# LED_Array.net
KiCad netlist of a schematic drawn in Altium Designer
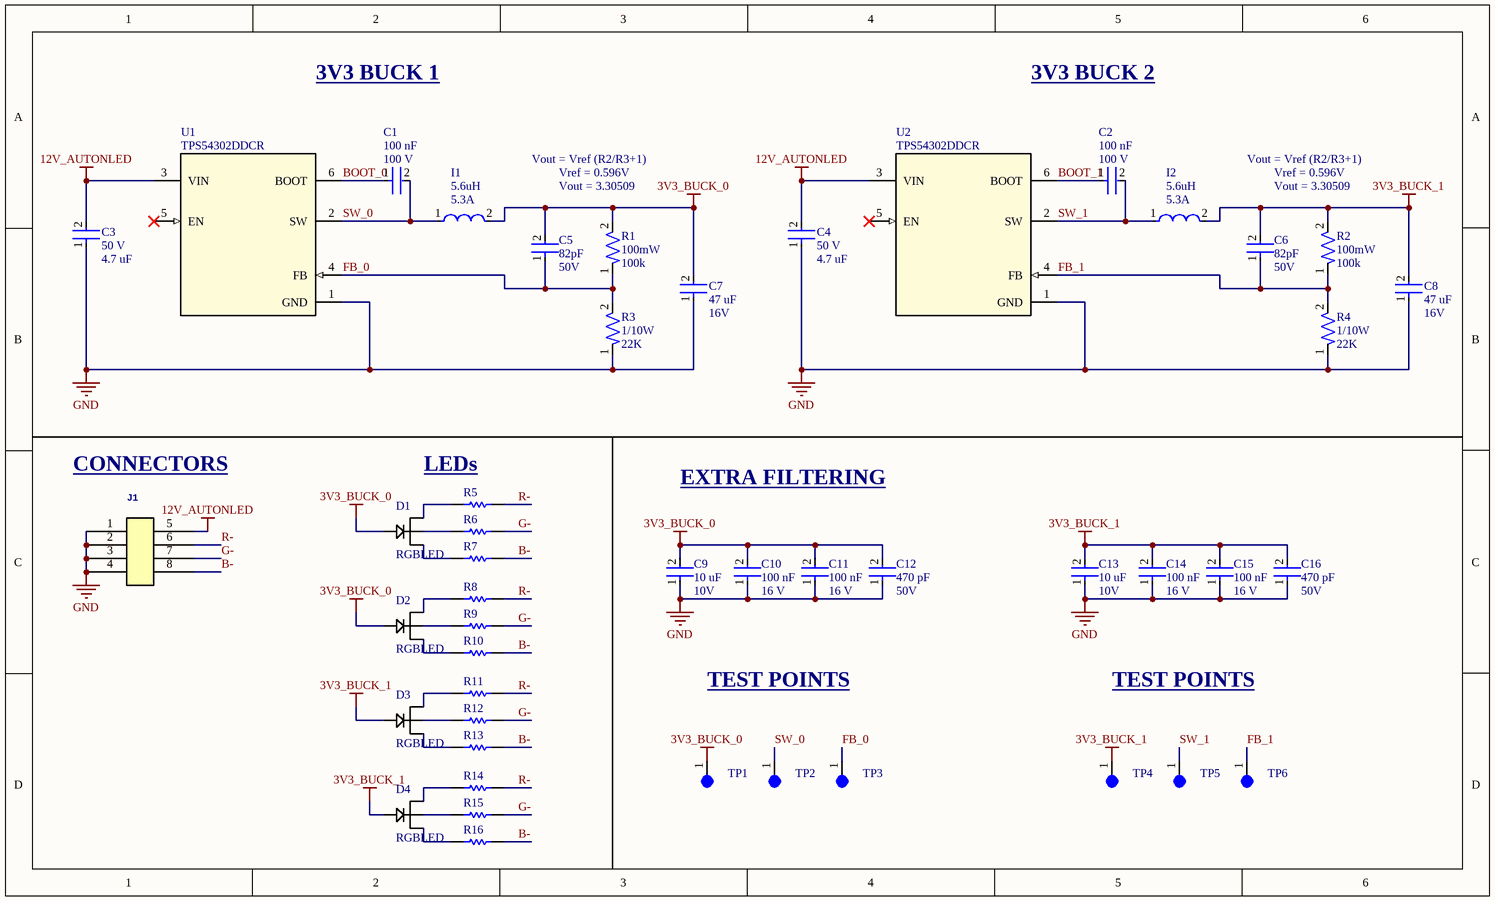
[diagram p0: LED_Array.SchDoc]

(export (version "E")
  (design (tool "Eeschema 10.0.6"))
  (components
    (comp (ref "C1")
      (value "CC0603KRX7R0BB104")
      (footprint "CAP-0603")
      (description "CAP CER 0.1UF 100V X7R 0603")
      (fields (field (name "CAPACITANCE") "100 nF") (field (name "VOLTAGE") "100 V"))
      (libsource (lib "JLC_25") (part "CAP-100N-0001"))
    )
    (comp (ref "C2")
      (value "CC0603KRX7R0BB104")
      (footprint "CAP-0603")
      (description "CAP CER 0.1UF 100V X7R 0603")
      (fields (field (name "CAPACITANCE") "100 nF") (field (name "VOLTAGE") "100 V"))
      (libsource (lib "JLC_25") (part "CAP-100N-0001"))
    )
    (comp (ref "C3")
      (value "CC0805KKX5R9BB475")
      (footprint "CAP-0805")
      (description "CAP CER 4.7UF 50V X5R 0805")
      (fields (field (name "VOLTAGE") "50 V") (field (name "CAPACITANCE") "4.7 uF"))
      (libsource (lib "JLC_25") (part "CAP-4.7U-0002"))
    )
    (comp (ref "C4")
      (value "CC0805KKX5R9BB475")
      (footprint "CAP-0805")
      (description "CAP CER 4.7UF 50V X5R 0805")
      (fields (field (name "VOLTAGE") "50 V") (field (name "CAPACITANCE") "4.7 uF"))
      (libsource (lib "JLC_25") (part "CAP-4.7U-0002"))
    )
    (comp (ref "C5")
      (value "CC0805JRNPO9BN820")
      (footprint "CAP-0805")
      (description "82 pF ±5% 50V Ceramic Capacitor C0G, NP0 0805 (2012 Metric)")
      (fields (field (name "VOLTAGE") "50V") (field (name "CAPACITANCE") "82pF"))
      (libsource (lib "JLC_25") (part "CAP-82P-0001"))
    )
    (comp (ref "C6")
      (value "CC0805JRNPO9BN820")
      (footprint "CAP-0805")
      (description "82 pF ±5% 50V Ceramic Capacitor C0G, NP0 0805 (2012 Metric)")
      (fields (field (name "VOLTAGE") "50V") (field (name "CAPACITANCE") "82pF"))
      (libsource (lib "JLC_25") (part "CAP-82P-0001"))
    )
    (comp (ref "C7")
      (value "GRM32ER61C476KE15L")
      (footprint "CAP-1210")
      (description "CAP CER 47UF 16V X5R 1210")
      (fields (field (name "CAPACITANCE") "47 uF") (field (name "VOLTAGE") "16V"))
      (libsource (lib "JLC_25") (part "CAP-47U-0002"))
    )
    (comp (ref "C8")
      (value "GRM32ER61C476KE15L")
      (footprint "CAP-1210")
      (description "CAP CER 47UF 16V X5R 1210")
      (fields (field (name "CAPACITANCE") "47 uF") (field (name "VOLTAGE") "16V"))
      (libsource (lib "JLC_25") (part "CAP-47U-0002"))
    )
    (comp (ref "C9")
      (value "CC0603KRX5R6BB106")
      (footprint "CAP-0603")
      (description "CAP CER 10UF 10V X5R 0603")
      (fields (field (name "VOLTAGE") "10V") (field (name "CAPACITANCE") "10 uF"))
      (libsource (lib "JLC_25") (part "CAP-10U-0001"))
    )
    (comp (ref "C10")
      (value "CC0402KRX7R7BB104")
      (footprint "CAP-0402")
      (description "CAP CER 0.1UF 16V X7R 0402")
      (fields (field (name "VOLTAGE RATING") "16 V") (field (name "CAPACITANCE") "100 nF"))
      (libsource (lib "JLC_25") (part "CAP-0.1U-0001"))
    )
    (comp (ref "C11")
      (value "CC0402KRX7R7BB104")
      (footprint "CAP-0402")
      (description "CAP CER 0.1UF 16V X7R 0402")
      (fields (field (name "VOLTAGE RATING") "16 V") (field (name "CAPACITANCE") "100 nF"))
      (libsource (lib "JLC_25") (part "CAP-0.1U-0001"))
    )
    (comp (ref "C12")
      (value "CC0805JRNPO9BN471")
      (footprint "CAP-0805")
      (description "CAP CER 470PF 50V C0G/NPO 0805")
      (fields (field (name "VOLTAGE") "50V") (field (name "CAPACITANCE") "470 pF"))
      (libsource (lib "JLC_25") (part "CAP-470P-0001"))
    )
    (comp (ref "C13")
      (value "CC0603KRX5R6BB106")
      (footprint "CAP-0603")
      (description "CAP CER 10UF 10V X5R 0603")
      (fields (field (name "VOLTAGE") "10V") (field (name "CAPACITANCE") "10 uF"))
      (libsource (lib "JLC_25") (part "CAP-10U-0001"))
    )
    (comp (ref "C14")
      (value "CC0402KRX7R7BB104")
      (footprint "CAP-0402")
      (description "CAP CER 0.1UF 16V X7R 0402")
      (fields (field (name "VOLTAGE RATING") "16 V") (field (name "CAPACITANCE") "100 nF"))
      (libsource (lib "JLC_25") (part "CAP-0.1U-0001"))
    )
    (comp (ref "C15")
      (value "CC0402KRX7R7BB104")
      (footprint "CAP-0402")
      (description "CAP CER 0.1UF 16V X7R 0402")
      (fields (field (name "VOLTAGE RATING") "16 V") (field (name "CAPACITANCE") "100 nF"))
      (libsource (lib "JLC_25") (part "CAP-0.1U-0001"))
    )
    (comp (ref "C16")
      (value "CC0805JRNPO9BN471")
      (footprint "CAP-0805")
      (description "CAP CER 470PF 50V C0G/NPO 0805")
      (fields (field (name "VOLTAGE") "50V") (field (name "CAPACITANCE") "470 pF"))
      (libsource (lib "JLC_25") (part "CAP-470P-0001"))
    )
    (comp (ref "D1")
      (value "RGBLED")
      (footprint "RGBLED")
      (libsource (lib "RoverTransistors") (part "RGBLED"))
    )
    (comp (ref "D2")
      (value "RGBLED")
      (footprint "RGBLED")
      (libsource (lib "RoverTransistors") (part "RGBLED"))
    )
    (comp (ref "D3")
      (value "RGBLED")
      (footprint "RGBLED")
      (libsource (lib "RoverTransistors") (part "RGBLED"))
    )
    (comp (ref "D4")
      (value "RGBLED")
      (footprint "RGBLED")
      (libsource (lib "RoverTransistors") (part "RGBLED"))
    )
    (comp (ref "I1")
      (value "ASPI-1306T-5R6M-T")
      (footprint "IND-5.6UH-0001")
      (description "5.6 µH Unshielded Drum Core, Wirewound Inductor 5.3 A 20mOhm Max Nonstandard")
      (fields (field (name "SATURATION CURRENT") "5.3A") (field (name "INDUCTANCE") "5.6uH"))
      (libsource (lib "JLC_25") (part "IND-5.6U-0001"))
    )
    (comp (ref "I2")
      (value "ASPI-1306T-5R6M-T")
      (footprint "IND-5.6UH-0001")
      (description "5.6 µH Unshielded Drum Core, Wirewound Inductor 5.3 A 20mOhm Max Nonstandard")
      (fields (field (name "SATURATION CURRENT") "5.3A") (field (name "INDUCTANCE") "5.6uH"))
      (libsource (lib "JLC_25") (part "IND-5.6U-0001"))
    )
    (comp (ref "J1")
      (value "Molex 43045-0812")
      (footprint "CONN-8POS-0001")
      (libsource (lib "JLC_25") (part "CONN-8POS-0001"))
    )
    (comp (ref "R1")
      (value "RC0603FR-07100KL")
      (footprint "RES-0603")
      (description "RES SMD 100K OHM 1% 1/10W 0603")
      (fields
        (field (name "TOLERANCE") "1%")
        (field (name "POWER") "100mW")
        (field (name "RESISTANCE") "100k")
      )
      (libsource (lib "JLC_25") (part "RES-100k-0001"))
    )
    (comp (ref "R2")
      (value "RC0603FR-07100KL")
      (footprint "RES-0603")
      (description "RES SMD 100K OHM 1% 1/10W 0603")
      (fields
        (field (name "TOLERANCE") "1%")
        (field (name "POWER") "100mW")
        (field (name "RESISTANCE") "100k")
      )
      (libsource (lib "JLC_25") (part "RES-100k-0001"))
    )
    (comp (ref "R3")
      (value "RC0603FR-0722KL")
      (footprint "RES-0603")
      (description "22 kOhms ±1% 0.1W, 1/10W Chip Resistor 0603 (1608 Metric) Moisture Resistant Thick Film")
      (fields (field (name "POWER") "1/10W") (field (name "RESISTANCE") "22K"))
      (libsource (lib "JLC_25") (part "RES-22k-0001"))
    )
    (comp (ref "R4")
      (value "RC0603FR-0722KL")
      (footprint "RES-0603")
      (description "22 kOhms ±1% 0.1W, 1/10W Chip Resistor 0603 (1608 Metric) Moisture Resistant Thick Film")
      (fields (field (name "POWER") "1/10W") (field (name "RESISTANCE") "22K"))
      (libsource (lib "JLC_25") (part "RES-22k-0001"))
    )
    (comp (ref "R5")
      (value "Res1")
      (footprint "AXIAL-0.3")
      (description "Resistor")
      (fields (field (name "PUBLISHER") "Altium Limited"))
      (libsource (lib "Miscellaneous Devices") (part "Res1"))
    )
    (comp (ref "R6")
      (value "Res1")
      (footprint "AXIAL-0.3")
      (description "Resistor")
      (fields (field (name "PUBLISHER") "Altium Limited"))
      (libsource (lib "Miscellaneous Devices") (part "Res1"))
    )
    (comp (ref "R7")
      (value "Res1")
      (footprint "AXIAL-0.3")
      (description "Resistor")
      (fields (field (name "PUBLISHER") "Altium Limited"))
      (libsource (lib "Miscellaneous Devices") (part "Res1"))
    )
    (comp (ref "R8")
      (value "Res1")
      (footprint "AXIAL-0.3")
      (description "Resistor")
      (fields (field (name "PUBLISHER") "Altium Limited"))
      (libsource (lib "Miscellaneous Devices") (part "Res1"))
    )
    (comp (ref "R9")
      (value "Res1")
      (footprint "AXIAL-0.3")
      (description "Resistor")
      (fields (field (name "PUBLISHER") "Altium Limited"))
      (libsource (lib "Miscellaneous Devices") (part "Res1"))
    )
    (comp (ref "R10")
      (value "Res1")
      (footprint "AXIAL-0.3")
      (description "Resistor")
      (fields (field (name "PUBLISHER") "Altium Limited"))
      (libsource (lib "Miscellaneous Devices") (part "Res1"))
    )
    (comp (ref "R11")
      (value "Res1")
      (footprint "AXIAL-0.3")
      (description "Resistor")
      (fields (field (name "PUBLISHER") "Altium Limited"))
      (libsource (lib "Miscellaneous Devices") (part "Res1"))
    )
    (comp (ref "R12")
      (value "Res1")
      (footprint "AXIAL-0.3")
      (description "Resistor")
      (fields (field (name "PUBLISHER") "Altium Limited"))
      (libsource (lib "Miscellaneous Devices") (part "Res1"))
    )
    (comp (ref "R13")
      (value "Res1")
      (footprint "AXIAL-0.3")
      (description "Resistor")
      (fields (field (name "PUBLISHER") "Altium Limited"))
      (libsource (lib "Miscellaneous Devices") (part "Res1"))
    )
    (comp (ref "R14")
      (value "Res1")
      (footprint "AXIAL-0.3")
      (description "Resistor")
      (fields (field (name "PUBLISHER") "Altium Limited"))
      (libsource (lib "Miscellaneous Devices") (part "Res1"))
    )
    (comp (ref "R15")
      (value "Res1")
      (footprint "AXIAL-0.3")
      (description "Resistor")
      (fields (field (name "PUBLISHER") "Altium Limited"))
      (libsource (lib "Miscellaneous Devices") (part "Res1"))
    )
    (comp (ref "R16")
      (value "Res1")
      (footprint "AXIAL-0.3")
      (description "Resistor")
      (fields (field (name "PUBLISHER") "Altium Limited"))
      (libsource (lib "Miscellaneous Devices") (part "Res1"))
    )
    (comp (ref "TP1")
      (value "5003")
      (footprint "TEST-POINT-0001")
      (description "Oranange PC Test Point, Miniature Phoisphor Bronze Silver Plating Through Hole Mounting Type")
      (libsource (lib "*") (part "TEST-POINT-0001"))
    )
    (comp (ref "TP2")
      (value "5003")
      (footprint "TEST-POINT-0001")
      (description "Oranange PC Test Point, Miniature Phoisphor Bronze Silver Plating Through Hole Mounting Type")
      (libsource (lib "*") (part "TEST-POINT-0001"))
    )
    (comp (ref "TP3")
      (value "5003")
      (footprint "TEST-POINT-0001")
      (description "Oranange PC Test Point, Miniature Phoisphor Bronze Silver Plating Through Hole Mounting Type")
      (libsource (lib "*") (part "TEST-POINT-0001"))
    )
    (comp (ref "TP4")
      (value "5003")
      (footprint "TEST-POINT-0001")
      (description "Oranange PC Test Point, Miniature Phoisphor Bronze Silver Plating Through Hole Mounting Type")
      (libsource (lib "*") (part "TEST-POINT-0001"))
    )
    (comp (ref "TP5")
      (value "5003")
      (footprint "TEST-POINT-0001")
      (description "Oranange PC Test Point, Miniature Phoisphor Bronze Silver Plating Through Hole Mounting Type")
      (libsource (lib "*") (part "TEST-POINT-0001"))
    )
    (comp (ref "TP6")
      (value "5003")
      (footprint "TEST-POINT-0001")
      (description "Oranange PC Test Point, Miniature Phoisphor Bronze Silver Plating Through Hole Mounting Type")
      (libsource (lib "*") (part "TEST-POINT-0001"))
    )
    (comp (ref "U1")
      (value "TPS54302DDCR")
      (footprint "IC-SOT-23-6")
      (description "IC REG BUCK ADJ 3A SOT23")
      (libsource (lib "JLC_25") (part "IC-BUCK-0004"))
    )
    (comp (ref "U2")
      (value "TPS54302DDCR")
      (footprint "IC-SOT-23-6")
      (description "IC REG BUCK ADJ 3A SOT23")
      (libsource (lib "JLC_25") (part "IC-BUCK-0004"))
    )
  )
  (nets
    (net (code "1") (name "/B-") (class "Default")
      (node (ref "J1") (pin "8") (pinfunction "8_8") (pintype "passive"))
      (node (ref "R10") (pin "2") (pinfunction "2_2") (pintype "passive"))
      (node (ref "R13") (pin "2") (pinfunction "2_2") (pintype "passive"))
      (node (ref "R16") (pin "2") (pinfunction "2_2") (pintype "passive"))
      (node (ref "R7") (pin "2") (pinfunction "2_2") (pintype "passive"))
    )
    (net (code "2") (name "/BOOT_0") (class "Default")
      (node (ref "C1") (pin "1") (pinfunction "1_1") (pintype "passive"))
      (node (ref "U1") (pin "6") (pinfunction "BOOT_6") (pintype "power_in"))
    )
    (net (code "3") (name "/BOOT_1") (class "Default")
      (node (ref "C2") (pin "1") (pinfunction "1_1") (pintype "passive"))
      (node (ref "U2") (pin "6") (pinfunction "BOOT_6") (pintype "power_in"))
    )
    (net (code "4") (name "/FB_0") (class "Default")
      (node (ref "C5") (pin "1") (pinfunction "1_1") (pintype "passive"))
      (node (ref "R1") (pin "1") (pinfunction "1_1") (pintype "passive"))
      (node (ref "R3") (pin "2") (pinfunction "2_2") (pintype "passive"))
      (node (ref "TP3") (pin "1") (pinfunction "0_1") (pintype "passive"))
      (node (ref "U1") (pin "4") (pinfunction "FB_4") (pintype "input"))
    )
    (net (code "5") (name "/FB_1") (class "Default")
      (node (ref "C6") (pin "1") (pinfunction "1_1") (pintype "passive"))
      (node (ref "R2") (pin "1") (pinfunction "1_1") (pintype "passive"))
      (node (ref "R4") (pin "2") (pinfunction "2_2") (pintype "passive"))
      (node (ref "TP6") (pin "1") (pinfunction "0_1") (pintype "passive"))
      (node (ref "U2") (pin "4") (pinfunction "FB_4") (pintype "input"))
    )
    (net (code "6") (name "/G-") (class "Default")
      (node (ref "J1") (pin "7") (pinfunction "7_7") (pintype "passive"))
      (node (ref "R12") (pin "2") (pinfunction "2_2") (pintype "passive"))
      (node (ref "R15") (pin "2") (pinfunction "2_2") (pintype "passive"))
      (node (ref "R6") (pin "2") (pinfunction "2_2") (pintype "passive"))
      (node (ref "R9") (pin "2") (pinfunction "2_2") (pintype "passive"))
    )
    (net (code "7") (name "/R-") (class "Default")
      (node (ref "J1") (pin "6") (pinfunction "6_6") (pintype "passive"))
      (node (ref "R11") (pin "2") (pinfunction "2_2") (pintype "passive"))
      (node (ref "R14") (pin "2") (pinfunction "2_2") (pintype "passive"))
      (node (ref "R5") (pin "2") (pinfunction "2_2") (pintype "passive"))
      (node (ref "R8") (pin "2") (pinfunction "2_2") (pintype "passive"))
    )
    (net (code "8") (name "/SW_0") (class "Default")
      (node (ref "C1") (pin "2") (pinfunction "2_2") (pintype "passive"))
      (node (ref "I1") (pin "1") (pinfunction "1_1") (pintype "passive"))
      (node (ref "TP2") (pin "1") (pinfunction "0_1") (pintype "passive"))
      (node (ref "U1") (pin "2") (pinfunction "SW_2") (pintype "power_in"))
    )
    (net (code "9") (name "/SW_1") (class "Default")
      (node (ref "C2") (pin "2") (pinfunction "2_2") (pintype "passive"))
      (node (ref "I2") (pin "1") (pinfunction "1_1") (pintype "passive"))
      (node (ref "TP5") (pin "1") (pinfunction "0_1") (pintype "passive"))
      (node (ref "U2") (pin "2") (pinfunction "SW_2") (pintype "power_in"))
    )
    (net (code "10") (name "3V3_BUCK_0") (class "Default")
      (node (ref "C10") (pin "2") (pinfunction "2_2") (pintype "passive"))
      (node (ref "C11") (pin "2") (pinfunction "2_2") (pintype "passive"))
      (node (ref "C12") (pin "2") (pinfunction "2_2") (pintype "passive"))
      (node (ref "C5") (pin "2") (pinfunction "2_2") (pintype "passive"))
      (node (ref "C7") (pin "2") (pinfunction "2_2") (pintype "passive"))
      (node (ref "C9") (pin "2") (pinfunction "2_2") (pintype "passive"))
      (node (ref "D1") (pin "0") (pinfunction "7_0") (pintype "passive"))
      (node (ref "D2") (pin "0") (pinfunction "7_0") (pintype "passive"))
      (node (ref "I1") (pin "2") (pinfunction "2_2") (pintype "passive"))
      (node (ref "R1") (pin "2") (pinfunction "2_2") (pintype "passive"))
      (node (ref "TP1") (pin "1") (pinfunction "0_1") (pintype "passive"))
    )
    (net (code "11") (name "3V3_BUCK_1") (class "Default")
      (node (ref "C13") (pin "2") (pinfunction "2_2") (pintype "passive"))
      (node (ref "C14") (pin "2") (pinfunction "2_2") (pintype "passive"))
      (node (ref "C15") (pin "2") (pinfunction "2_2") (pintype "passive"))
      (node (ref "C16") (pin "2") (pinfunction "2_2") (pintype "passive"))
      (node (ref "C6") (pin "2") (pinfunction "2_2") (pintype "passive"))
      (node (ref "C8") (pin "2") (pinfunction "2_2") (pintype "passive"))
      (node (ref "D3") (pin "0") (pinfunction "7_0") (pintype "passive"))
      (node (ref "D4") (pin "0") (pinfunction "7_0") (pintype "passive"))
      (node (ref "I2") (pin "2") (pinfunction "2_2") (pintype "passive"))
      (node (ref "R2") (pin "2") (pinfunction "2_2") (pintype "passive"))
      (node (ref "TP4") (pin "1") (pinfunction "0_1") (pintype "passive"))
    )
    (net (code "12") (name "12V_AUTONLED") (class "Default")
      (node (ref "C3") (pin "2") (pinfunction "2_2") (pintype "passive"))
      (node (ref "C4") (pin "2") (pinfunction "2_2") (pintype "passive"))
      (node (ref "J1") (pin "5") (pinfunction "5_5") (pintype "passive"))
      (node (ref "U1") (pin "3") (pinfunction "VIN_3") (pintype "power_in"))
      (node (ref "U2") (pin "3") (pinfunction "VIN_3") (pintype "power_in"))
    )
    (net (code "13") (name "GND") (class "Default")
      (node (ref "C10") (pin "1") (pinfunction "1_1") (pintype "passive"))
      (node (ref "C11") (pin "1") (pinfunction "1_1") (pintype "passive"))
      (node (ref "C12") (pin "1") (pinfunction "1_1") (pintype "passive"))
      (node (ref "C13") (pin "1") (pinfunction "1_1") (pintype "passive"))
      (node (ref "C14") (pin "1") (pinfunction "1_1") (pintype "passive"))
      (node (ref "C15") (pin "1") (pinfunction "1_1") (pintype "passive"))
      (node (ref "C16") (pin "1") (pinfunction "1_1") (pintype "passive"))
      (node (ref "C3") (pin "1") (pinfunction "1_1") (pintype "passive"))
      (node (ref "C4") (pin "1") (pinfunction "1_1") (pintype "passive"))
      (node (ref "C7") (pin "1") (pinfunction "1_1") (pintype "passive"))
      (node (ref "C8") (pin "1") (pinfunction "1_1") (pintype "passive"))
      (node (ref "C9") (pin "1") (pinfunction "1_1") (pintype "passive"))
      (node (ref "J1") (pin "1") (pinfunction "7_1") (pintype "passive"))
      (node (ref "J1") (pin "2") (pinfunction "2_2") (pintype "passive"))
      (node (ref "J1") (pin "3") (pinfunction "3_3") (pintype "passive"))
      (node (ref "J1") (pin "4") (pinfunction "4_4") (pintype "passive"))
      (node (ref "R3") (pin "1") (pinfunction "1_1") (pintype "passive"))
      (node (ref "R4") (pin "1") (pinfunction "1_1") (pintype "passive"))
      (node (ref "U1") (pin "1") (pinfunction "GND_1") (pintype "power_in"))
      (node (ref "U2") (pin "1") (pinfunction "GND_1") (pintype "power_in"))
    )
    (net (code "14") (name "Net-(D1-B-)") (class "Default")
      (node (ref "D1") (pin "3") (pinfunction "B-_3") (pintype "passive"))
      (node (ref "R7") (pin "1") (pinfunction "1_1") (pintype "passive"))
    )
    (net (code "15") (name "Net-(D1-G-)") (class "Default")
      (node (ref "D1") (pin "2") (pinfunction "G-_2") (pintype "passive"))
      (node (ref "R6") (pin "1") (pinfunction "1_1") (pintype "passive"))
    )
    (net (code "16") (name "Net-(D1-R-)") (class "Default")
      (node (ref "D1") (pin "1") (pinfunction "R-_1") (pintype "passive"))
      (node (ref "R5") (pin "1") (pinfunction "1_1") (pintype "passive"))
    )
    (net (code "17") (name "Net-(D2-B-)") (class "Default")
      (node (ref "D2") (pin "3") (pinfunction "B-_3") (pintype "passive"))
      (node (ref "R10") (pin "1") (pinfunction "1_1") (pintype "passive"))
    )
    (net (code "18") (name "Net-(D2-G-)") (class "Default")
      (node (ref "D2") (pin "2") (pinfunction "G-_2") (pintype "passive"))
      (node (ref "R9") (pin "1") (pinfunction "1_1") (pintype "passive"))
    )
    (net (code "19") (name "Net-(D2-R-)") (class "Default")
      (node (ref "D2") (pin "1") (pinfunction "R-_1") (pintype "passive"))
      (node (ref "R8") (pin "1") (pinfunction "1_1") (pintype "passive"))
    )
    (net (code "20") (name "Net-(D3-B-)") (class "Default")
      (node (ref "D3") (pin "3") (pinfunction "B-_3") (pintype "passive"))
      (node (ref "R13") (pin "1") (pinfunction "1_1") (pintype "passive"))
    )
    (net (code "21") (name "Net-(D3-G-)") (class "Default")
      (node (ref "D3") (pin "2") (pinfunction "G-_2") (pintype "passive"))
      (node (ref "R12") (pin "1") (pinfunction "1_1") (pintype "passive"))
    )
    (net (code "22") (name "Net-(D3-R-)") (class "Default")
      (node (ref "D3") (pin "1") (pinfunction "R-_1") (pintype "passive"))
      (node (ref "R11") (pin "1") (pinfunction "1_1") (pintype "passive"))
    )
    (net (code "23") (name "Net-(D4-B-)") (class "Default")
      (node (ref "D4") (pin "3") (pinfunction "B-_3") (pintype "passive"))
      (node (ref "R16") (pin "1") (pinfunction "1_1") (pintype "passive"))
    )
    (net (code "24") (name "Net-(D4-G-)") (class "Default")
      (node (ref "D4") (pin "2") (pinfunction "G-_2") (pintype "passive"))
      (node (ref "R15") (pin "1") (pinfunction "1_1") (pintype "passive"))
    )
    (net (code "25") (name "Net-(D4-R-)") (class "Default")
      (node (ref "D4") (pin "1") (pinfunction "R-_1") (pintype "passive"))
      (node (ref "R14") (pin "1") (pinfunction "1_1") (pintype "passive"))
    )
    (net (code "26") (name "unconnected-(U1-EN-Pad5)") (class "Default")
      (node (ref "U1") (pin "5") (pinfunction "EN_5") (pintype "input+no_connect"))
    )
    (net (code "27") (name "unconnected-(U2-EN-Pad5)") (class "Default")
      (node (ref "U2") (pin "5") (pinfunction "EN_5") (pintype "input+no_connect"))
    )
  )
)
